# fonte1.net
KiCad netlist of a schematic drawn in EAGLE
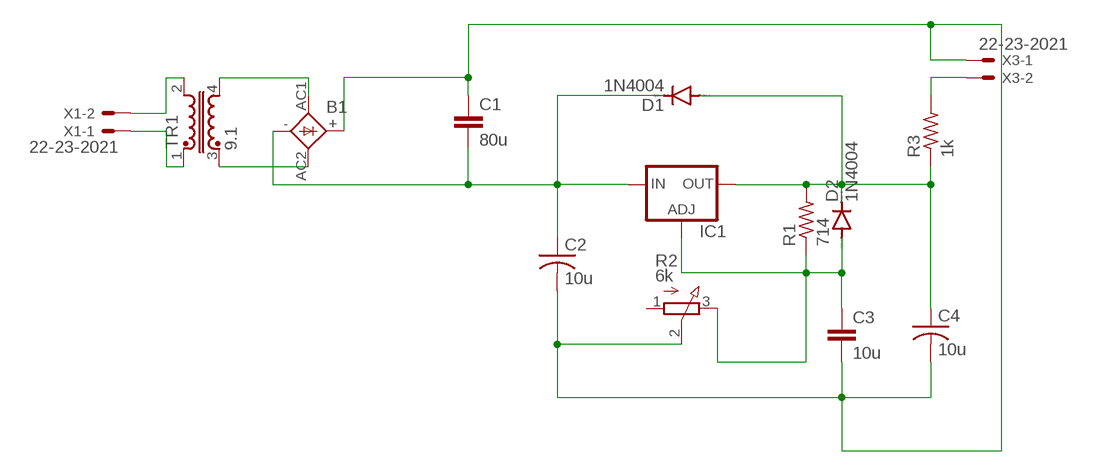
[diagram p0: schematic, sheet 1]

(export (version "E")
  (design (tool "Eeschema 10.0.6"))
  (components
    (comp (ref "B1")
      (value "1KAB")
      (footprint "eagle-import:1KAB")
      (libsource (lib "eagle-import") (part "1KAB"))
    )
    (comp (ref "C1")
      (value "80u")
      (footprint "eagle-import:C025-025X050")
      (libsource (lib "eagle-import") (part "C-EU025-025X050"))
    )
    (comp (ref "C2")
      (value "10u")
      (footprint "eagle-import:C025-024X044")
      (libsource (lib "eagle-import") (part "C-US025-024X044"))
    )
    (comp (ref "C3")
      (value "10u")
      (footprint "eagle-import:C025-025X050")
      (libsource (lib "eagle-import") (part "C-EU025-025X050"))
    )
    (comp (ref "C4")
      (value "10u")
      (footprint "eagle-import:C025-024X044")
      (libsource (lib "eagle-import") (part "C-US025-024X044"))
    )
    (comp (ref "D1")
      (value "1N4004")
      (footprint "eagle-import:DO41-10")
      (libsource (lib "eagle-import") (part "1N4004"))
    )
    (comp (ref "D2")
      (value "1N4004")
      (footprint "eagle-import:DO41-10")
      (libsource (lib "eagle-import") (part "1N4004"))
    )
    (comp (ref "IC1")
      (value "LM317TL")
      (footprint "eagle-import:317TL")
      (libsource (lib "eagle-import") (part "LM317TL"))
    )
    (comp (ref "R1")
      (value "714")
      (footprint "eagle-import:0204_7")
      (libsource (lib "eagle-import") (part "R-US_0204/7"))
    )
    (comp (ref "R2")
      (value "6k")
      (footprint "eagle-import:3RP_1610N")
      (libsource (lib "eagle-import") (part "3RP/1610N"))
    )
    (comp (ref "R3")
      (value "1k")
      (footprint "eagle-import:0204_7")
      (libsource (lib "eagle-import") (part "R-US_0204/7"))
    )
    (comp (ref "TR1")
      (value "9.1")
      (footprint "eagle-import:U15")
      (libsource (lib "eagle-import") (part "U15-TRANSFORMER"))
    )
    (comp (ref "X1")
      (value "22-23-2021")
      (footprint "eagle-import:22-23-2021")
      (fields (field (name "MF") "MOLEX"))
      (libsource (lib "eagle-import") (part "22-23-2021"))
    )
    (comp (ref "X3")
      (value "22-23-2021")
      (footprint "eagle-import:22-23-2021")
      (fields (field (name "MF") "MOLEX"))
      (libsource (lib "eagle-import") (part "22-23-2021"))
    )
  )
  (nets
    (net (code "1") (name "Net-(B1-PadAC1)") (class "Default")
      (node (ref "B1") (pin "AC1") (pinfunction "AC1_AC1") (pintype "passive"))
      (node (ref "TR1") (pin "4") (pinfunction "4_4") (pintype "passive"))
    )
    (net (code "2") (name "Net-(B1-PadAC2)") (class "Default")
      (node (ref "B1") (pin "AC2") (pinfunction "AC2_AC2") (pintype "passive"))
      (node (ref "TR1") (pin "3") (pinfunction "3_3") (pintype "passive"))
    )
    (net (code "3") (name "Net-(IC1-ADJ)") (class "Default")
      (node (ref "C3") (pin "1") (pinfunction "1_1") (pintype "passive"))
      (node (ref "D2") (pin "A") (pinfunction "A_A") (pintype "passive"))
      (node (ref "IC1") (pin "1") (pinfunction "ADJ_1") (pintype "input"))
      (node (ref "R1") (pin "1") (pinfunction "1_1") (pintype "passive"))
      (node (ref "R2") (pin "3") (pinfunction "E_3") (pintype "passive"))
    )
    (net (code "4") (name "Net-(IC1-IN)") (class "Default")
      (node (ref "B1") (pin "-") (pinfunction "-_-") (pintype "passive"))
      (node (ref "C1") (pin "2") (pinfunction "2_2") (pintype "passive"))
      (node (ref "C2") (pin "1") (pinfunction "1_1") (pintype "passive"))
      (node (ref "D1") (pin "C") (pinfunction "C_C") (pintype "passive"))
      (node (ref "IC1") (pin "3") (pinfunction "IN_3") (pintype "input"))
    )
    (net (code "5") (name "Net-(IC1-OUT)") (class "Default")
      (node (ref "C4") (pin "1") (pinfunction "1_1") (pintype "passive"))
      (node (ref "D1") (pin "A") (pinfunction "A_A") (pintype "passive"))
      (node (ref "D2") (pin "C") (pinfunction "C_C") (pintype "passive"))
      (node (ref "IC1") (pin "2") (pinfunction "OUT_2") (pintype "passive"))
      (node (ref "R1") (pin "2") (pinfunction "2_2") (pintype "passive"))
      (node (ref "R3") (pin "1") (pinfunction "1_1") (pintype "passive"))
    )
    (net (code "6") (name "Net-(R2-S)") (class "Default")
      (node (ref "B1") (pin "+") (pinfunction "+_+") (pintype "passive"))
      (node (ref "C1") (pin "1") (pinfunction "1_1") (pintype "passive"))
      (node (ref "C2") (pin "2") (pinfunction "2_2") (pintype "passive"))
      (node (ref "C3") (pin "2") (pinfunction "2_2") (pintype "passive"))
      (node (ref "C4") (pin "2") (pinfunction "2_2") (pintype "passive"))
      (node (ref "R2") (pin "2") (pinfunction "S_2") (pintype "passive"))
      (node (ref "X3") (pin "1") (pinfunction "S_1") (pintype "passive"))
    )
    (net (code "7") (name "Net-(X1A-S)") (class "Default")
      (node (ref "TR1") (pin "1") (pinfunction "1_1") (pintype "passive"))
      (node (ref "X1") (pin "1") (pinfunction "S_1") (pintype "passive"))
    )
    (net (code "8") (name "Net-(X1B-S)") (class "Default")
      (node (ref "TR1") (pin "2") (pinfunction "2_2") (pintype "passive"))
      (node (ref "X1") (pin "2") (pinfunction "S_2") (pintype "passive"))
    )
    (net (code "9") (name "Net-(X3B-S)") (class "Default")
      (node (ref "R3") (pin "2") (pinfunction "2_2") (pintype "passive"))
      (node (ref "X3") (pin "2") (pinfunction "S_2") (pintype "passive"))
    )
    (net (code "10") (name "unconnected-(R2-A-Pad1)") (class "Default")
      (node (ref "R2") (pin "1") (pinfunction "A_1") (pintype "passive"))
    )
  )
)
